# LEDChain2.net
KiCad netlist of a schematic drawn in Altium Designer
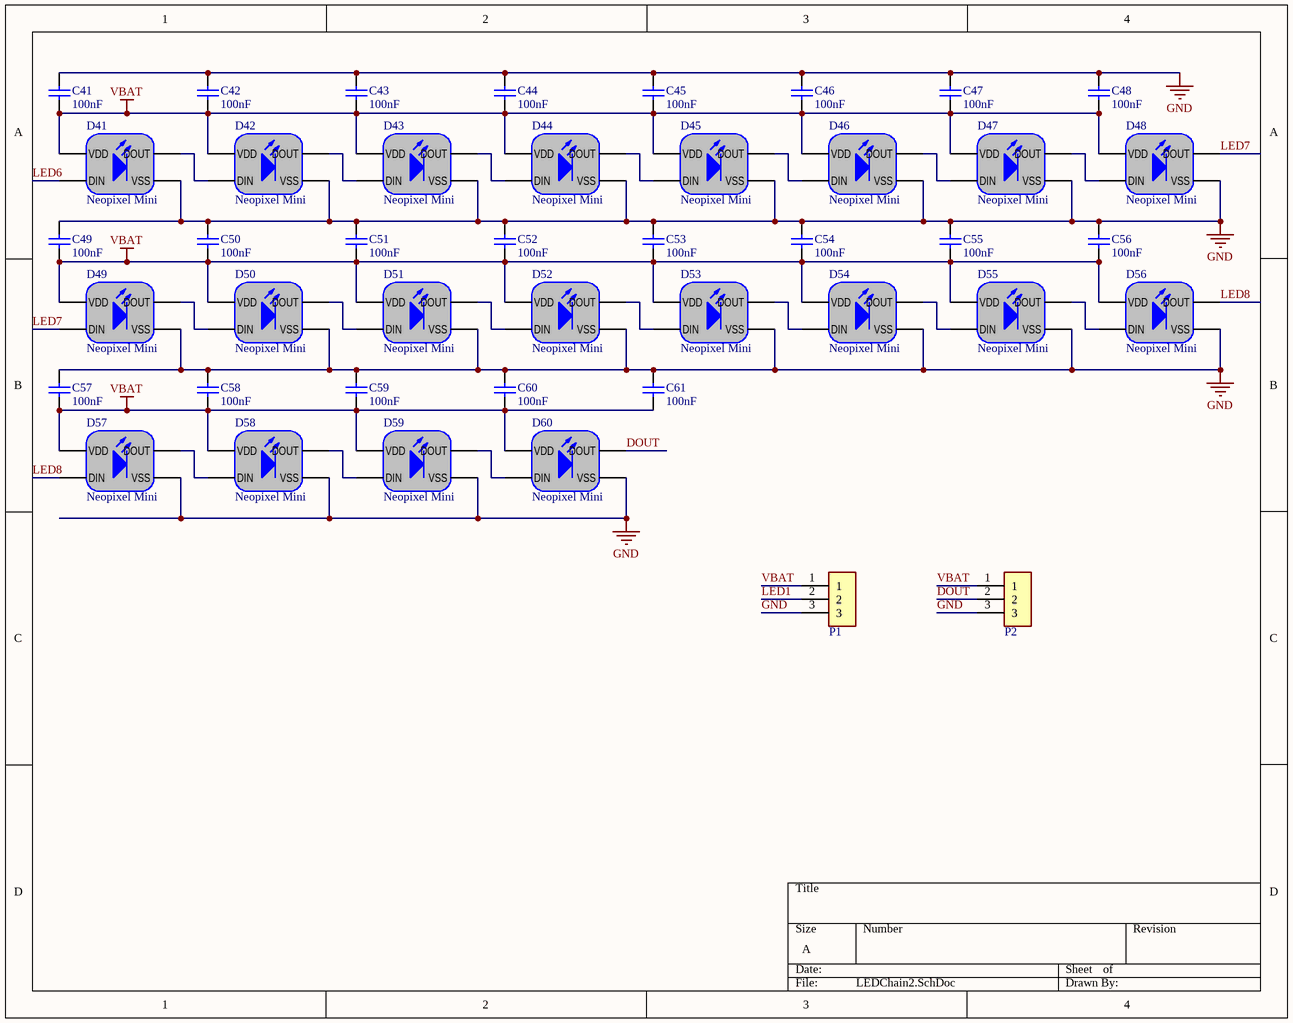
[diagram p0: LEDChain2.SchDoc]

(export (version "E")
  (design (tool "Eeschema 10.0.6"))
  (components
    (comp (ref "C41")
      (value "100nF")
      (footprint "0402_CAP")
      (description "CAP CER 0.1UF 16V X7R 0402")
      (fields (field (name "PUBLISHER") "Altium Limited"))
      (libsource (lib "Common Passives") (part "CAP_100N_0603"))
    )
    (comp (ref "C42")
      (value "100nF")
      (footprint "0402_CAP")
      (description "CAP CER 0.1UF 16V X7R 0402")
      (fields (field (name "PUBLISHER") "Altium Limited"))
      (libsource (lib "Common Passives") (part "CAP_100N_0603"))
    )
    (comp (ref "C43")
      (value "100nF")
      (footprint "0402_CAP")
      (description "CAP CER 0.1UF 16V X7R 0402")
      (fields (field (name "PUBLISHER") "Altium Limited"))
      (libsource (lib "Common Passives") (part "CAP_100N_0603"))
    )
    (comp (ref "C44")
      (value "100nF")
      (footprint "0402_CAP")
      (description "CAP CER 0.1UF 16V X7R 0402")
      (fields (field (name "PUBLISHER") "Altium Limited"))
      (libsource (lib "Common Passives") (part "CAP_100N_0603"))
    )
    (comp (ref "C45")
      (value "100nF")
      (footprint "0402_CAP")
      (description "CAP CER 0.1UF 16V X7R 0402")
      (fields (field (name "PUBLISHER") "Altium Limited"))
      (libsource (lib "Common Passives") (part "CAP_100N_0603"))
    )
    (comp (ref "C46")
      (value "100nF")
      (footprint "0402_CAP")
      (description "CAP CER 0.1UF 16V X7R 0402")
      (fields (field (name "PUBLISHER") "Altium Limited"))
      (libsource (lib "Common Passives") (part "CAP_100N_0603"))
    )
    (comp (ref "C47")
      (value "100nF")
      (footprint "0402_CAP")
      (description "CAP CER 0.1UF 16V X7R 0402")
      (fields (field (name "PUBLISHER") "Altium Limited"))
      (libsource (lib "Common Passives") (part "CAP_100N_0603"))
    )
    (comp (ref "C48")
      (value "100nF")
      (footprint "0402_CAP")
      (description "CAP CER 0.1UF 16V X7R 0402")
      (fields (field (name "PUBLISHER") "Altium Limited"))
      (libsource (lib "Common Passives") (part "CAP_100N_0603"))
    )
    (comp (ref "C49")
      (value "100nF")
      (footprint "0402_CAP")
      (description "CAP CER 0.1UF 16V X7R 0402")
      (fields (field (name "PUBLISHER") "Altium Limited"))
      (libsource (lib "Common Passives") (part "CAP_100N_0603"))
    )
    (comp (ref "C50")
      (value "100nF")
      (footprint "0402_CAP")
      (description "CAP CER 0.1UF 16V X7R 0402")
      (fields (field (name "PUBLISHER") "Altium Limited"))
      (libsource (lib "Common Passives") (part "CAP_100N_0603"))
    )
    (comp (ref "C51")
      (value "100nF")
      (footprint "0402_CAP")
      (description "CAP CER 0.1UF 16V X7R 0402")
      (fields (field (name "PUBLISHER") "Altium Limited"))
      (libsource (lib "Common Passives") (part "CAP_100N_0603"))
    )
    (comp (ref "C52")
      (value "100nF")
      (footprint "0402_CAP")
      (description "CAP CER 0.1UF 16V X7R 0402")
      (fields (field (name "PUBLISHER") "Altium Limited"))
      (libsource (lib "Common Passives") (part "CAP_100N_0603"))
    )
    (comp (ref "C53")
      (value "100nF")
      (footprint "0402_CAP")
      (description "CAP CER 0.1UF 16V X7R 0402")
      (fields (field (name "PUBLISHER") "Altium Limited"))
      (libsource (lib "Common Passives") (part "CAP_100N_0603"))
    )
    (comp (ref "C54")
      (value "100nF")
      (footprint "0402_CAP")
      (description "CAP CER 0.1UF 16V X7R 0402")
      (fields (field (name "PUBLISHER") "Altium Limited"))
      (libsource (lib "Common Passives") (part "CAP_100N_0603"))
    )
    (comp (ref "C55")
      (value "100nF")
      (footprint "0402_CAP")
      (description "CAP CER 0.1UF 16V X7R 0402")
      (fields (field (name "PUBLISHER") "Altium Limited"))
      (libsource (lib "Common Passives") (part "CAP_100N_0603"))
    )
    (comp (ref "C56")
      (value "100nF")
      (footprint "0402_CAP")
      (description "CAP CER 0.1UF 16V X7R 0402")
      (fields (field (name "PUBLISHER") "Altium Limited"))
      (libsource (lib "Common Passives") (part "CAP_100N_0603"))
    )
    (comp (ref "C57")
      (value "100nF")
      (footprint "0402_CAP")
      (description "CAP CER 0.1UF 16V X7R 0402")
      (fields (field (name "PUBLISHER") "Altium Limited"))
      (libsource (lib "Common Passives") (part "CAP_100N_0603"))
    )
    (comp (ref "C58")
      (value "100nF")
      (footprint "0402_CAP")
      (description "CAP CER 0.1UF 16V X7R 0402")
      (fields (field (name "PUBLISHER") "Altium Limited"))
      (libsource (lib "Common Passives") (part "CAP_100N_0603"))
    )
    (comp (ref "C59")
      (value "100nF")
      (footprint "0402_CAP")
      (description "CAP CER 0.1UF 16V X7R 0402")
      (fields (field (name "PUBLISHER") "Altium Limited"))
      (libsource (lib "Common Passives") (part "CAP_100N_0603"))
    )
    (comp (ref "C60")
      (value "100nF")
      (footprint "0402_CAP")
      (description "CAP CER 0.1UF 16V X7R 0402")
      (fields (field (name "PUBLISHER") "Altium Limited"))
      (libsource (lib "Common Passives") (part "CAP_100N_0603"))
    )
    (comp (ref "C61")
      (value "100nF")
      (footprint "0402_CAP")
      (description "CAP CER 0.1UF 16V X7R 0402")
      (fields (field (name "PUBLISHER") "Altium Limited"))
      (libsource (lib "Common Passives") (part "CAP_100N_0603"))
    )
    (comp (ref "D41")
      (value "Neopixel Mini")
      (footprint "SK6812 (3535)")
      (description "ADDRESS LED DISC SERIAL RGB")
      (libsource (lib "Diodes") (part "SK6812MINI-B-001"))
    )
    (comp (ref "D42")
      (value "Neopixel Mini")
      (footprint "SK6812 (3535)")
      (description "ADDRESS LED DISC SERIAL RGB")
      (libsource (lib "Diodes") (part "SK6812MINI-B-001"))
    )
    (comp (ref "D43")
      (value "Neopixel Mini")
      (footprint "SK6812 (3535)")
      (description "ADDRESS LED DISC SERIAL RGB")
      (libsource (lib "Diodes") (part "SK6812MINI-B-001"))
    )
    (comp (ref "D44")
      (value "Neopixel Mini")
      (footprint "SK6812 (3535)")
      (description "ADDRESS LED DISC SERIAL RGB")
      (libsource (lib "Diodes") (part "SK6812MINI-B-001"))
    )
    (comp (ref "D45")
      (value "Neopixel Mini")
      (footprint "SK6812 (3535)")
      (description "ADDRESS LED DISC SERIAL RGB")
      (libsource (lib "Diodes") (part "SK6812MINI-B-001"))
    )
    (comp (ref "D46")
      (value "Neopixel Mini")
      (footprint "SK6812 (3535)")
      (description "ADDRESS LED DISC SERIAL RGB")
      (libsource (lib "Diodes") (part "SK6812MINI-B-001"))
    )
    (comp (ref "D47")
      (value "Neopixel Mini")
      (footprint "SK6812 (3535)")
      (description "ADDRESS LED DISC SERIAL RGB")
      (libsource (lib "Diodes") (part "SK6812MINI-B-001"))
    )
    (comp (ref "D48")
      (value "Neopixel Mini")
      (footprint "SK6812 (3535)")
      (description "ADDRESS LED DISC SERIAL RGB")
      (libsource (lib "Diodes") (part "SK6812MINI-B-001"))
    )
    (comp (ref "D49")
      (value "Neopixel Mini")
      (footprint "SK6812 (3535)")
      (description "ADDRESS LED DISC SERIAL RGB")
      (libsource (lib "Diodes") (part "SK6812MINI-B-001"))
    )
    (comp (ref "D50")
      (value "Neopixel Mini")
      (footprint "SK6812 (3535)")
      (description "ADDRESS LED DISC SERIAL RGB")
      (libsource (lib "Diodes") (part "SK6812MINI-B-001"))
    )
    (comp (ref "D51")
      (value "Neopixel Mini")
      (footprint "SK6812 (3535)")
      (description "ADDRESS LED DISC SERIAL RGB")
      (libsource (lib "Diodes") (part "SK6812MINI-B-001"))
    )
    (comp (ref "D52")
      (value "Neopixel Mini")
      (footprint "SK6812 (3535)")
      (description "ADDRESS LED DISC SERIAL RGB")
      (libsource (lib "Diodes") (part "SK6812MINI-B-001"))
    )
    (comp (ref "D53")
      (value "Neopixel Mini")
      (footprint "SK6812 (3535)")
      (description "ADDRESS LED DISC SERIAL RGB")
      (libsource (lib "Diodes") (part "SK6812MINI-B-001"))
    )
    (comp (ref "D54")
      (value "Neopixel Mini")
      (footprint "SK6812 (3535)")
      (description "ADDRESS LED DISC SERIAL RGB")
      (libsource (lib "Diodes") (part "SK6812MINI-B-001"))
    )
    (comp (ref "D55")
      (value "Neopixel Mini")
      (footprint "SK6812 (3535)")
      (description "ADDRESS LED DISC SERIAL RGB")
      (libsource (lib "Diodes") (part "SK6812MINI-B-001"))
    )
    (comp (ref "D56")
      (value "Neopixel Mini")
      (footprint "SK6812 (3535)")
      (description "ADDRESS LED DISC SERIAL RGB")
      (libsource (lib "Diodes") (part "SK6812MINI-B-001"))
    )
    (comp (ref "D57")
      (value "Neopixel Mini")
      (footprint "SK6812 (3535)")
      (description "ADDRESS LED DISC SERIAL RGB")
      (libsource (lib "Diodes") (part "SK6812MINI-B-001"))
    )
    (comp (ref "D58")
      (value "Neopixel Mini")
      (footprint "SK6812 (3535)")
      (description "ADDRESS LED DISC SERIAL RGB")
      (libsource (lib "Diodes") (part "SK6812MINI-B-001"))
    )
    (comp (ref "D59")
      (value "Neopixel Mini")
      (footprint "SK6812 (3535)")
      (description "ADDRESS LED DISC SERIAL RGB")
      (libsource (lib "Diodes") (part "SK6812MINI-B-001"))
    )
    (comp (ref "D60")
      (value "Neopixel Mini")
      (footprint "SK6812 (3535)")
      (description "ADDRESS LED DISC SERIAL RGB")
      (libsource (lib "Diodes") (part "SK6812MINI-B-001"))
    )
    (comp (ref "P1")
      (value "HEADER_1x3_TIGHT")
      (footprint "PIN3 - TIGHT")
      (libsource (lib "Connectors") (part "HEADER_1x3_TIGHT"))
    )
    (comp (ref "P2")
      (value "HEADER_1x3_TIGHT")
      (footprint "PIN3 - TIGHT")
      (libsource (lib "Connectors") (part "HEADER_1x3_TIGHT"))
    )
  )
  (nets
    (net (code "1") (name "/DOUT") (class "Default")
      (node (ref "D60") (pin "1") (pinfunction "DOUT_1") (pintype "passive"))
      (node (ref "P2") (pin "2") (pinfunction "2_2") (pintype "passive"))
    )
    (net (code "2") (name "/LED1") (class "Default")
      (node (ref "P1") (pin "2") (pinfunction "2_2") (pintype "passive"))
    )
    (net (code "3") (name "/LED6") (class "Default")
      (node (ref "D41") (pin "3") (pinfunction "DIN_3") (pintype "passive"))
    )
    (net (code "4") (name "/LED7") (class "Default")
      (node (ref "D48") (pin "1") (pinfunction "DOUT_1") (pintype "passive"))
      (node (ref "D49") (pin "3") (pinfunction "DIN_3") (pintype "passive"))
    )
    (net (code "5") (name "/LED8") (class "Default")
      (node (ref "D56") (pin "1") (pinfunction "DOUT_1") (pintype "passive"))
      (node (ref "D57") (pin "3") (pinfunction "DIN_3") (pintype "passive"))
    )
    (net (code "6") (name "GND") (class "Default")
      (node (ref "C41") (pin "2") (pinfunction "2_2") (pintype "passive"))
      (node (ref "C42") (pin "2") (pinfunction "2_2") (pintype "passive"))
      (node (ref "C43") (pin "2") (pinfunction "2_2") (pintype "passive"))
      (node (ref "C44") (pin "2") (pinfunction "2_2") (pintype "passive"))
      (node (ref "C45") (pin "2") (pinfunction "2_2") (pintype "passive"))
      (node (ref "C46") (pin "2") (pinfunction "2_2") (pintype "passive"))
      (node (ref "C47") (pin "2") (pinfunction "2_2") (pintype "passive"))
      (node (ref "C48") (pin "2") (pinfunction "2_2") (pintype "passive"))
      (node (ref "C49") (pin "2") (pinfunction "2_2") (pintype "passive"))
      (node (ref "C50") (pin "2") (pinfunction "2_2") (pintype "passive"))
      (node (ref "C51") (pin "2") (pinfunction "2_2") (pintype "passive"))
      (node (ref "C52") (pin "2") (pinfunction "2_2") (pintype "passive"))
      (node (ref "C53") (pin "2") (pinfunction "2_2") (pintype "passive"))
      (node (ref "C54") (pin "2") (pinfunction "2_2") (pintype "passive"))
      (node (ref "C55") (pin "2") (pinfunction "2_2") (pintype "passive"))
      (node (ref "C56") (pin "2") (pinfunction "2_2") (pintype "passive"))
      (node (ref "C57") (pin "2") (pinfunction "2_2") (pintype "passive"))
      (node (ref "C58") (pin "2") (pinfunction "2_2") (pintype "passive"))
      (node (ref "C59") (pin "2") (pinfunction "2_2") (pintype "passive"))
      (node (ref "C60") (pin "2") (pinfunction "2_2") (pintype "passive"))
      (node (ref "C61") (pin "2") (pinfunction "2_2") (pintype "passive"))
      (node (ref "D41") (pin "2") (pinfunction "VSS_2") (pintype "passive"))
      (node (ref "D42") (pin "2") (pinfunction "VSS_2") (pintype "passive"))
      (node (ref "D43") (pin "2") (pinfunction "VSS_2") (pintype "passive"))
      (node (ref "D44") (pin "2") (pinfunction "VSS_2") (pintype "passive"))
      (node (ref "D45") (pin "2") (pinfunction "VSS_2") (pintype "passive"))
      (node (ref "D46") (pin "2") (pinfunction "VSS_2") (pintype "passive"))
      (node (ref "D47") (pin "2") (pinfunction "VSS_2") (pintype "passive"))
      (node (ref "D48") (pin "2") (pinfunction "VSS_2") (pintype "passive"))
      (node (ref "D49") (pin "2") (pinfunction "VSS_2") (pintype "passive"))
      (node (ref "D50") (pin "2") (pinfunction "VSS_2") (pintype "passive"))
      (node (ref "D51") (pin "2") (pinfunction "VSS_2") (pintype "passive"))
      (node (ref "D52") (pin "2") (pinfunction "VSS_2") (pintype "passive"))
      (node (ref "D53") (pin "2") (pinfunction "VSS_2") (pintype "passive"))
      (node (ref "D54") (pin "2") (pinfunction "VSS_2") (pintype "passive"))
      (node (ref "D55") (pin "2") (pinfunction "VSS_2") (pintype "passive"))
      (node (ref "D56") (pin "2") (pinfunction "VSS_2") (pintype "passive"))
      (node (ref "D57") (pin "2") (pinfunction "VSS_2") (pintype "passive"))
      (node (ref "D58") (pin "2") (pinfunction "VSS_2") (pintype "passive"))
      (node (ref "D59") (pin "2") (pinfunction "VSS_2") (pintype "passive"))
      (node (ref "D60") (pin "2") (pinfunction "VSS_2") (pintype "passive"))
      (node (ref "P1") (pin "3") (pinfunction "3_3") (pintype "passive"))
      (node (ref "P2") (pin "3") (pinfunction "3_3") (pintype "passive"))
    )
    (net (code "7") (name "Net-(D41-DOUT)") (class "Default")
      (node (ref "D41") (pin "1") (pinfunction "DOUT_1") (pintype "passive"))
      (node (ref "D42") (pin "3") (pinfunction "DIN_3") (pintype "passive"))
    )
    (net (code "8") (name "Net-(D42-DOUT)") (class "Default")
      (node (ref "D42") (pin "1") (pinfunction "DOUT_1") (pintype "passive"))
      (node (ref "D43") (pin "3") (pinfunction "DIN_3") (pintype "passive"))
    )
    (net (code "9") (name "Net-(D43-DOUT)") (class "Default")
      (node (ref "D43") (pin "1") (pinfunction "DOUT_1") (pintype "passive"))
      (node (ref "D44") (pin "3") (pinfunction "DIN_3") (pintype "passive"))
    )
    (net (code "10") (name "Net-(D44-DOUT)") (class "Default")
      (node (ref "D44") (pin "1") (pinfunction "DOUT_1") (pintype "passive"))
      (node (ref "D45") (pin "3") (pinfunction "DIN_3") (pintype "passive"))
    )
    (net (code "11") (name "Net-(D45-DOUT)") (class "Default")
      (node (ref "D45") (pin "1") (pinfunction "DOUT_1") (pintype "passive"))
      (node (ref "D46") (pin "3") (pinfunction "DIN_3") (pintype "passive"))
    )
    (net (code "12") (name "Net-(D46-DOUT)") (class "Default")
      (node (ref "D46") (pin "1") (pinfunction "DOUT_1") (pintype "passive"))
      (node (ref "D47") (pin "3") (pinfunction "DIN_3") (pintype "passive"))
    )
    (net (code "13") (name "Net-(D47-DOUT)") (class "Default")
      (node (ref "D47") (pin "1") (pinfunction "DOUT_1") (pintype "passive"))
      (node (ref "D48") (pin "3") (pinfunction "DIN_3") (pintype "passive"))
    )
    (net (code "14") (name "Net-(D49-DOUT)") (class "Default")
      (node (ref "D49") (pin "1") (pinfunction "DOUT_1") (pintype "passive"))
      (node (ref "D50") (pin "3") (pinfunction "DIN_3") (pintype "passive"))
    )
    (net (code "15") (name "Net-(D50-DOUT)") (class "Default")
      (node (ref "D50") (pin "1") (pinfunction "DOUT_1") (pintype "passive"))
      (node (ref "D51") (pin "3") (pinfunction "DIN_3") (pintype "passive"))
    )
    (net (code "16") (name "Net-(D51-DOUT)") (class "Default")
      (node (ref "D51") (pin "1") (pinfunction "DOUT_1") (pintype "passive"))
      (node (ref "D52") (pin "3") (pinfunction "DIN_3") (pintype "passive"))
    )
    (net (code "17") (name "Net-(D52-DOUT)") (class "Default")
      (node (ref "D52") (pin "1") (pinfunction "DOUT_1") (pintype "passive"))
      (node (ref "D53") (pin "3") (pinfunction "DIN_3") (pintype "passive"))
    )
    (net (code "18") (name "Net-(D53-DOUT)") (class "Default")
      (node (ref "D53") (pin "1") (pinfunction "DOUT_1") (pintype "passive"))
      (node (ref "D54") (pin "3") (pinfunction "DIN_3") (pintype "passive"))
    )
    (net (code "19") (name "Net-(D54-DOUT)") (class "Default")
      (node (ref "D54") (pin "1") (pinfunction "DOUT_1") (pintype "passive"))
      (node (ref "D55") (pin "3") (pinfunction "DIN_3") (pintype "passive"))
    )
    (net (code "20") (name "Net-(D55-DOUT)") (class "Default")
      (node (ref "D55") (pin "1") (pinfunction "DOUT_1") (pintype "passive"))
      (node (ref "D56") (pin "3") (pinfunction "DIN_3") (pintype "passive"))
    )
    (net (code "21") (name "Net-(D57-DOUT)") (class "Default")
      (node (ref "D57") (pin "1") (pinfunction "DOUT_1") (pintype "passive"))
      (node (ref "D58") (pin "3") (pinfunction "DIN_3") (pintype "passive"))
    )
    (net (code "22") (name "Net-(D58-DOUT)") (class "Default")
      (node (ref "D58") (pin "1") (pinfunction "DOUT_1") (pintype "passive"))
      (node (ref "D59") (pin "3") (pinfunction "DIN_3") (pintype "passive"))
    )
    (net (code "23") (name "Net-(D59-DOUT)") (class "Default")
      (node (ref "D59") (pin "1") (pinfunction "DOUT_1") (pintype "passive"))
      (node (ref "D60") (pin "3") (pinfunction "DIN_3") (pintype "passive"))
    )
    (net (code "24") (name "VBAT") (class "Default")
      (node (ref "C41") (pin "1") (pinfunction "1_1") (pintype "passive"))
      (node (ref "C42") (pin "1") (pinfunction "1_1") (pintype "passive"))
      (node (ref "C43") (pin "1") (pinfunction "1_1") (pintype "passive"))
      (node (ref "C44") (pin "1") (pinfunction "1_1") (pintype "passive"))
      (node (ref "C45") (pin "1") (pinfunction "1_1") (pintype "passive"))
      (node (ref "C46") (pin "1") (pinfunction "1_1") (pintype "passive"))
      (node (ref "C47") (pin "1") (pinfunction "1_1") (pintype "passive"))
      (node (ref "C48") (pin "1") (pinfunction "1_1") (pintype "passive"))
      (node (ref "C49") (pin "1") (pinfunction "1_1") (pintype "passive"))
      (node (ref "C50") (pin "1") (pinfunction "1_1") (pintype "passive"))
      (node (ref "C51") (pin "1") (pinfunction "1_1") (pintype "passive"))
      (node (ref "C52") (pin "1") (pinfunction "1_1") (pintype "passive"))
      (node (ref "C53") (pin "1") (pinfunction "1_1") (pintype "passive"))
      (node (ref "C54") (pin "1") (pinfunction "1_1") (pintype "passive"))
      (node (ref "C55") (pin "1") (pinfunction "1_1") (pintype "passive"))
      (node (ref "C56") (pin "1") (pinfunction "1_1") (pintype "passive"))
      (node (ref "C57") (pin "1") (pinfunction "1_1") (pintype "passive"))
      (node (ref "C58") (pin "1") (pinfunction "1_1") (pintype "passive"))
      (node (ref "C59") (pin "1") (pinfunction "1_1") (pintype "passive"))
      (node (ref "C60") (pin "1") (pinfunction "1_1") (pintype "passive"))
      (node (ref "C61") (pin "1") (pinfunction "1_1") (pintype "passive"))
      (node (ref "D41") (pin "4") (pinfunction "VDD_4") (pintype "passive"))
      (node (ref "D42") (pin "4") (pinfunction "VDD_4") (pintype "passive"))
      (node (ref "D43") (pin "4") (pinfunction "VDD_4") (pintype "passive"))
      (node (ref "D44") (pin "4") (pinfunction "VDD_4") (pintype "passive"))
      (node (ref "D45") (pin "4") (pinfunction "VDD_4") (pintype "passive"))
      (node (ref "D46") (pin "4") (pinfunction "VDD_4") (pintype "passive"))
      (node (ref "D47") (pin "4") (pinfunction "VDD_4") (pintype "passive"))
      (node (ref "D48") (pin "4") (pinfunction "VDD_4") (pintype "passive"))
      (node (ref "D49") (pin "4") (pinfunction "VDD_4") (pintype "passive"))
      (node (ref "D50") (pin "4") (pinfunction "VDD_4") (pintype "passive"))
      (node (ref "D51") (pin "4") (pinfunction "VDD_4") (pintype "passive"))
      (node (ref "D52") (pin "4") (pinfunction "VDD_4") (pintype "passive"))
      (node (ref "D53") (pin "4") (pinfunction "VDD_4") (pintype "passive"))
      (node (ref "D54") (pin "4") (pinfunction "VDD_4") (pintype "passive"))
      (node (ref "D55") (pin "4") (pinfunction "VDD_4") (pintype "passive"))
      (node (ref "D56") (pin "4") (pinfunction "VDD_4") (pintype "passive"))
      (node (ref "D57") (pin "4") (pinfunction "VDD_4") (pintype "passive"))
      (node (ref "D58") (pin "4") (pinfunction "VDD_4") (pintype "passive"))
      (node (ref "D59") (pin "4") (pinfunction "VDD_4") (pintype "passive"))
      (node (ref "D60") (pin "4") (pinfunction "VDD_4") (pintype "passive"))
      (node (ref "P1") (pin "1") (pinfunction "1_1") (pintype "passive"))
      (node (ref "P2") (pin "1") (pinfunction "1_1") (pintype "passive"))
    )
  )
)
